# SAS_Connectors.net
KiCad netlist of a schematic drawn in Altium Designer
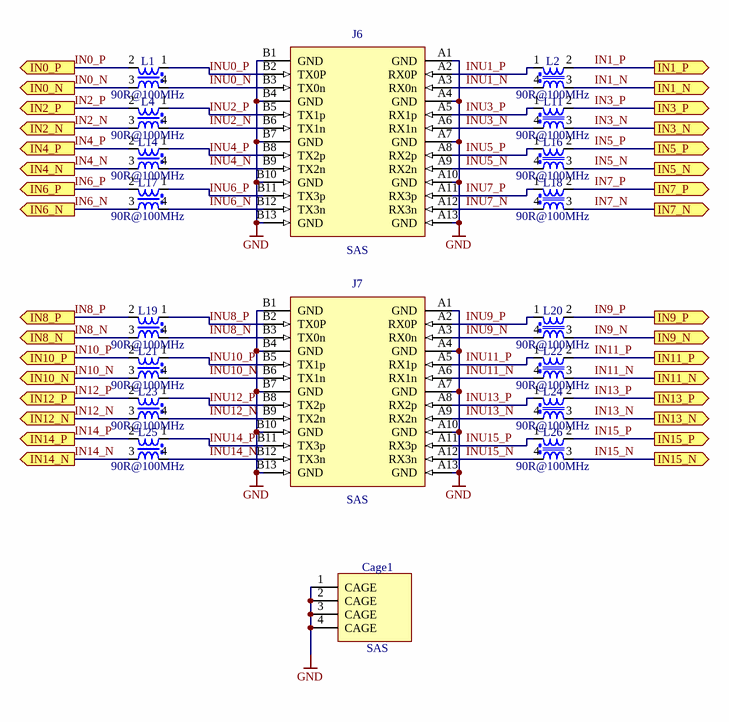
[diagram p0: SAS_Connectors.SchDoc]

(export (version "E")
  (design (tool "Eeschema 10.0.6"))
  (components
    (comp (ref "Cage1")
      (value "SAS")
      (footprint "TYCO_1888321-2")
      (description "SAS 2x1 Cage")
      (fields
        (field (name "PART NUMBER") "TYCO_1888321-2")
        (field (name "MANUFACTURER") "TYCO ELECTRONICS")
        (field (name "AUTHOR") "GK")
      )
      (libsource (lib "LIBRARY_SCH") (part "CON_SAS_Cage"))
    )
    (comp (ref "J6")
      (value "SAS")
      (footprint "TYCO_1761987-7")
      (description "26Position mini SAS Connector")
      (fields
        (field (name "PART NUMBER") "TYCO_1761987-7")
        (field (name "MANUFACTURER") "TYCO ELECTRONICS")
        (field (name "AUTHOR") "GK")
      )
      (libsource (lib "LIBRARY_SCH") (part "CON_SAS_1761987-7"))
    )
    (comp (ref "J7")
      (value "SAS")
      (footprint "TYCO_1761987-7")
      (description "26Position mini SAS Connector")
      (fields
        (field (name "PART NUMBER") "TYCO_1761987-7")
        (field (name "MANUFACTURER") "TYCO ELECTRONICS")
        (field (name "AUTHOR") "GK")
      )
      (libsource (lib "LIBRARY_SCH") (part "CON_SAS_1761987-7"))
    )
    (comp (ref "L1")
      (value "90R@100MHz")
      (footprint "IND_MURATA_DLW21S")
      (description "Inductor Common Mode")
      (fields
        (field (name "PART NUMBER") "IND_MURATA_DLW21SN900SQ2L")
        (field (name "POWER") "330mA")
        (field (name "AUTHOR") "CERN DEM JLC")
      )
      (libsource (lib "") (part "Inductor Common Mode 1Dot-2 4Dot-3_1"))
    )
    (comp (ref "L2")
      (value "90R@100MHz")
      (footprint "IND_MURATA_DLW21S")
      (description "Inductor Common Mode")
      (fields
        (field (name "PART NUMBER") "IND_MURATA_DLW21SN900SQ2L")
        (field (name "POWER") "330mA")
        (field (name "AUTHOR") "CERN DEM JLC")
      )
      (libsource (lib "Inductors & Transformers") (part "Inductor Common Mode 1Dot-2 4Dot-3"))
    )
    (comp (ref "L4")
      (value "90R@100MHz")
      (footprint "IND_MURATA_DLW21S")
      (description "Inductor Common Mode")
      (fields
        (field (name "PART NUMBER") "IND_MURATA_DLW21SN900SQ2L")
        (field (name "POWER") "330mA")
        (field (name "AUTHOR") "CERN DEM JLC")
      )
      (libsource (lib "") (part "Inductor Common Mode 1Dot-2 4Dot-3_1"))
    )
    (comp (ref "L11")
      (value "90R@100MHz")
      (footprint "IND_MURATA_DLW21S")
      (description "Inductor Common Mode")
      (fields
        (field (name "PART NUMBER") "IND_MURATA_DLW21SN900SQ2L")
        (field (name "POWER") "330mA")
        (field (name "AUTHOR") "CERN DEM JLC")
      )
      (libsource (lib "Inductors & Transformers") (part "Inductor Common Mode 1Dot-2 4Dot-3"))
    )
    (comp (ref "L14")
      (value "90R@100MHz")
      (footprint "IND_MURATA_DLW21S")
      (description "Inductor Common Mode")
      (fields
        (field (name "PART NUMBER") "IND_MURATA_DLW21SN900SQ2L")
        (field (name "POWER") "330mA")
        (field (name "AUTHOR") "CERN DEM JLC")
      )
      (libsource (lib "") (part "Inductor Common Mode 1Dot-2 4Dot-3_1"))
    )
    (comp (ref "L16")
      (value "90R@100MHz")
      (footprint "IND_MURATA_DLW21S")
      (description "Inductor Common Mode")
      (fields
        (field (name "PART NUMBER") "IND_MURATA_DLW21SN900SQ2L")
        (field (name "POWER") "330mA")
        (field (name "AUTHOR") "CERN DEM JLC")
      )
      (libsource (lib "Inductors & Transformers") (part "Inductor Common Mode 1Dot-2 4Dot-3"))
    )
    (comp (ref "L17")
      (value "90R@100MHz")
      (footprint "IND_MURATA_DLW21S")
      (description "Inductor Common Mode")
      (fields
        (field (name "PART NUMBER") "IND_MURATA_DLW21SN900SQ2L")
        (field (name "POWER") "330mA")
        (field (name "AUTHOR") "CERN DEM JLC")
      )
      (libsource (lib "") (part "Inductor Common Mode 1Dot-2 4Dot-3_1"))
    )
    (comp (ref "L18")
      (value "90R@100MHz")
      (footprint "IND_MURATA_DLW21S")
      (description "Inductor Common Mode")
      (fields
        (field (name "PART NUMBER") "IND_MURATA_DLW21SN900SQ2L")
        (field (name "POWER") "330mA")
        (field (name "AUTHOR") "CERN DEM JLC")
      )
      (libsource (lib "Inductors & Transformers") (part "Inductor Common Mode 1Dot-2 4Dot-3"))
    )
    (comp (ref "L19")
      (value "90R@100MHz")
      (footprint "IND_MURATA_DLW21S")
      (description "Inductor Common Mode")
      (fields
        (field (name "PART NUMBER") "IND_MURATA_DLW21SN900SQ2L")
        (field (name "POWER") "330mA")
        (field (name "AUTHOR") "CERN DEM JLC")
      )
      (libsource (lib "") (part "Inductor Common Mode 1Dot-2 4Dot-3_1"))
    )
    (comp (ref "L20")
      (value "90R@100MHz")
      (footprint "IND_MURATA_DLW21S")
      (description "Inductor Common Mode")
      (fields
        (field (name "PART NUMBER") "IND_MURATA_DLW21SN900SQ2L")
        (field (name "POWER") "330mA")
        (field (name "AUTHOR") "CERN DEM JLC")
      )
      (libsource (lib "Inductors & Transformers") (part "Inductor Common Mode 1Dot-2 4Dot-3"))
    )
    (comp (ref "L21")
      (value "90R@100MHz")
      (footprint "IND_MURATA_DLW21S")
      (description "Inductor Common Mode")
      (fields
        (field (name "PART NUMBER") "IND_MURATA_DLW21SN900SQ2L")
        (field (name "POWER") "330mA")
        (field (name "AUTHOR") "CERN DEM JLC")
      )
      (libsource (lib "") (part "Inductor Common Mode 1Dot-2 4Dot-3_1"))
    )
    (comp (ref "L22")
      (value "90R@100MHz")
      (footprint "IND_MURATA_DLW21S")
      (description "Inductor Common Mode")
      (fields
        (field (name "PART NUMBER") "IND_MURATA_DLW21SN900SQ2L")
        (field (name "POWER") "330mA")
        (field (name "AUTHOR") "CERN DEM JLC")
      )
      (libsource (lib "Inductors & Transformers") (part "Inductor Common Mode 1Dot-2 4Dot-3"))
    )
    (comp (ref "L23")
      (value "90R@100MHz")
      (footprint "IND_MURATA_DLW21S")
      (description "Inductor Common Mode")
      (fields
        (field (name "PART NUMBER") "IND_MURATA_DLW21SN900SQ2L")
        (field (name "POWER") "330mA")
        (field (name "AUTHOR") "CERN DEM JLC")
      )
      (libsource (lib "") (part "Inductor Common Mode 1Dot-2 4Dot-3_1"))
    )
    (comp (ref "L24")
      (value "90R@100MHz")
      (footprint "IND_MURATA_DLW21S")
      (description "Inductor Common Mode")
      (fields
        (field (name "PART NUMBER") "IND_MURATA_DLW21SN900SQ2L")
        (field (name "POWER") "330mA")
        (field (name "AUTHOR") "CERN DEM JLC")
      )
      (libsource (lib "Inductors & Transformers") (part "Inductor Common Mode 1Dot-2 4Dot-3"))
    )
    (comp (ref "L25")
      (value "90R@100MHz")
      (footprint "IND_MURATA_DLW21S")
      (description "Inductor Common Mode")
      (fields
        (field (name "PART NUMBER") "IND_MURATA_DLW21SN900SQ2L")
        (field (name "POWER") "330mA")
        (field (name "AUTHOR") "CERN DEM JLC")
      )
      (libsource (lib "") (part "Inductor Common Mode 1Dot-2 4Dot-3_1"))
    )
    (comp (ref "L26")
      (value "90R@100MHz")
      (footprint "IND_MURATA_DLW21S")
      (description "Inductor Common Mode")
      (fields
        (field (name "PART NUMBER") "IND_MURATA_DLW21SN900SQ2L")
        (field (name "POWER") "330mA")
        (field (name "AUTHOR") "CERN DEM JLC")
      )
      (libsource (lib "Inductors & Transformers") (part "Inductor Common Mode 1Dot-2 4Dot-3"))
    )
  )
  (nets
    (net (code "1") (name "/IN0_N") (class "Default")
      (node (ref "L1") (pin "3") (pinfunction "3_3") (pintype "passive"))
    )
    (net (code "2") (name "/IN0_P") (class "Default")
      (node (ref "L1") (pin "2") (pinfunction "2_2") (pintype "passive"))
    )
    (net (code "3") (name "/IN1_N") (class "Default")
      (node (ref "L2") (pin "3") (pinfunction "3_3") (pintype "passive"))
    )
    (net (code "4") (name "/IN1_P") (class "Default")
      (node (ref "L2") (pin "2") (pinfunction "2_2") (pintype "passive"))
    )
    (net (code "5") (name "/IN2_N") (class "Default")
      (node (ref "L4") (pin "3") (pinfunction "3_3") (pintype "passive"))
    )
    (net (code "6") (name "/IN2_P") (class "Default")
      (node (ref "L4") (pin "2") (pinfunction "2_2") (pintype "passive"))
    )
    (net (code "7") (name "/IN3_N") (class "Default")
      (node (ref "L11") (pin "3") (pinfunction "3_3") (pintype "passive"))
    )
    (net (code "8") (name "/IN3_P") (class "Default")
      (node (ref "L11") (pin "2") (pinfunction "2_2") (pintype "passive"))
    )
    (net (code "9") (name "/IN4_N") (class "Default")
      (node (ref "L14") (pin "3") (pinfunction "3_3") (pintype "passive"))
    )
    (net (code "10") (name "/IN4_P") (class "Default")
      (node (ref "L14") (pin "2") (pinfunction "2_2") (pintype "passive"))
    )
    (net (code "11") (name "/IN5_N") (class "Default")
      (node (ref "L16") (pin "3") (pinfunction "3_3") (pintype "passive"))
    )
    (net (code "12") (name "/IN5_P") (class "Default")
      (node (ref "L16") (pin "2") (pinfunction "2_2") (pintype "passive"))
    )
    (net (code "13") (name "/IN6_N") (class "Default")
      (node (ref "L17") (pin "3") (pinfunction "3_3") (pintype "passive"))
    )
    (net (code "14") (name "/IN6_P") (class "Default")
      (node (ref "L17") (pin "2") (pinfunction "2_2") (pintype "passive"))
    )
    (net (code "15") (name "/IN7_N") (class "Default")
      (node (ref "L18") (pin "3") (pinfunction "3_3") (pintype "passive"))
    )
    (net (code "16") (name "/IN7_P") (class "Default")
      (node (ref "L18") (pin "2") (pinfunction "2_2") (pintype "passive"))
    )
    (net (code "17") (name "/IN8_N") (class "Default")
      (node (ref "L19") (pin "3") (pinfunction "3_3") (pintype "passive"))
    )
    (net (code "18") (name "/IN8_P") (class "Default")
      (node (ref "L19") (pin "2") (pinfunction "2_2") (pintype "passive"))
    )
    (net (code "19") (name "/IN9_N") (class "Default")
      (node (ref "L20") (pin "3") (pinfunction "3_3") (pintype "passive"))
    )
    (net (code "20") (name "/IN9_P") (class "Default")
      (node (ref "L20") (pin "2") (pinfunction "2_2") (pintype "passive"))
    )
    (net (code "21") (name "/IN10_N") (class "Default")
      (node (ref "L21") (pin "3") (pinfunction "3_3") (pintype "passive"))
    )
    (net (code "22") (name "/IN10_P") (class "Default")
      (node (ref "L21") (pin "2") (pinfunction "2_2") (pintype "passive"))
    )
    (net (code "23") (name "/IN11_N") (class "Default")
      (node (ref "L22") (pin "3") (pinfunction "3_3") (pintype "passive"))
    )
    (net (code "24") (name "/IN11_P") (class "Default")
      (node (ref "L22") (pin "2") (pinfunction "2_2") (pintype "passive"))
    )
    (net (code "25") (name "/IN12_N") (class "Default")
      (node (ref "L23") (pin "3") (pinfunction "3_3") (pintype "passive"))
    )
    (net (code "26") (name "/IN12_P") (class "Default")
      (node (ref "L23") (pin "2") (pinfunction "2_2") (pintype "passive"))
    )
    (net (code "27") (name "/IN13_N") (class "Default")
      (node (ref "L24") (pin "3") (pinfunction "3_3") (pintype "passive"))
    )
    (net (code "28") (name "/IN13_P") (class "Default")
      (node (ref "L24") (pin "2") (pinfunction "2_2") (pintype "passive"))
    )
    (net (code "29") (name "/IN14_N") (class "Default")
      (node (ref "L25") (pin "3") (pinfunction "3_3") (pintype "passive"))
    )
    (net (code "30") (name "/IN14_P") (class "Default")
      (node (ref "L25") (pin "2") (pinfunction "2_2") (pintype "passive"))
    )
    (net (code "31") (name "/IN15_N") (class "Default")
      (node (ref "L26") (pin "3") (pinfunction "3_3") (pintype "passive"))
    )
    (net (code "32") (name "/IN15_P") (class "Default")
      (node (ref "L26") (pin "2") (pinfunction "2_2") (pintype "passive"))
    )
    (net (code "33") (name "/INU0_N") (class "Default")
      (node (ref "J6") (pin "B3") (pinfunction "TX0n_B3") (pintype "input"))
      (node (ref "L1") (pin "4") (pinfunction "4_4") (pintype "passive"))
    )
    (net (code "34") (name "/INU0_P") (class "Default")
      (node (ref "J6") (pin "B2") (pinfunction "TX0P_B2") (pintype "input"))
      (node (ref "L1") (pin "1") (pinfunction "1_1") (pintype "passive"))
    )
    (net (code "35") (name "/INU1_N") (class "Default")
      (node (ref "J6") (pin "A3") (pinfunction "RX0n_A3") (pintype "input"))
      (node (ref "L2") (pin "4") (pinfunction "4_4") (pintype "passive"))
    )
    (net (code "36") (name "/INU1_P") (class "Default")
      (node (ref "J6") (pin "A2") (pinfunction "RX0P_A2") (pintype "input"))
      (node (ref "L2") (pin "1") (pinfunction "1_1") (pintype "passive"))
    )
    (net (code "37") (name "/INU2_N") (class "Default")
      (node (ref "J6") (pin "B6") (pinfunction "TX1n_B6") (pintype "input"))
      (node (ref "L4") (pin "4") (pinfunction "4_4") (pintype "passive"))
    )
    (net (code "38") (name "/INU2_P") (class "Default")
      (node (ref "J6") (pin "B5") (pinfunction "TX1p_B5") (pintype "input"))
      (node (ref "L4") (pin "1") (pinfunction "1_1") (pintype "passive"))
    )
    (net (code "39") (name "/INU3_N") (class "Default")
      (node (ref "J6") (pin "A6") (pinfunction "RX1n_A6") (pintype "input"))
      (node (ref "L11") (pin "4") (pinfunction "4_4") (pintype "passive"))
    )
    (net (code "40") (name "/INU3_P") (class "Default")
      (node (ref "J6") (pin "A5") (pinfunction "RX1p_A5") (pintype "input"))
      (node (ref "L11") (pin "1") (pinfunction "1_1") (pintype "passive"))
    )
    (net (code "41") (name "/INU4_N") (class "Default")
      (node (ref "J6") (pin "B9") (pinfunction "TX2n_B9") (pintype "input"))
      (node (ref "L14") (pin "4") (pinfunction "4_4") (pintype "passive"))
    )
    (net (code "42") (name "/INU4_P") (class "Default")
      (node (ref "J6") (pin "B8") (pinfunction "TX2p_B8") (pintype "input"))
      (node (ref "L14") (pin "1") (pinfunction "1_1") (pintype "passive"))
    )
    (net (code "43") (name "/INU5_N") (class "Default")
      (node (ref "J6") (pin "A9") (pinfunction "RX2n_A9") (pintype "input"))
      (node (ref "L16") (pin "4") (pinfunction "4_4") (pintype "passive"))
    )
    (net (code "44") (name "/INU5_P") (class "Default")
      (node (ref "J6") (pin "A8") (pinfunction "RX2p_A8") (pintype "input"))
      (node (ref "L16") (pin "1") (pinfunction "1_1") (pintype "passive"))
    )
    (net (code "45") (name "/INU6_N") (class "Default")
      (node (ref "J6") (pin "B12") (pinfunction "TX3n_B12") (pintype "input"))
      (node (ref "L17") (pin "4") (pinfunction "4_4") (pintype "passive"))
    )
    (net (code "46") (name "/INU6_P") (class "Default")
      (node (ref "J6") (pin "B11") (pinfunction "TX3p_B11") (pintype "input"))
      (node (ref "L17") (pin "1") (pinfunction "1_1") (pintype "passive"))
    )
    (net (code "47") (name "/INU7_N") (class "Default")
      (node (ref "J6") (pin "A12") (pinfunction "RX3n_A12") (pintype "input"))
      (node (ref "L18") (pin "4") (pinfunction "4_4") (pintype "passive"))
    )
    (net (code "48") (name "/INU7_P") (class "Default")
      (node (ref "J6") (pin "A11") (pinfunction "RX3p_A11") (pintype "input"))
      (node (ref "L18") (pin "1") (pinfunction "1_1") (pintype "passive"))
    )
    (net (code "49") (name "/INU8_N") (class "Default")
      (node (ref "J7") (pin "B3") (pinfunction "TX0n_B3") (pintype "input"))
      (node (ref "L19") (pin "4") (pinfunction "4_4") (pintype "passive"))
    )
    (net (code "50") (name "/INU8_P") (class "Default")
      (node (ref "J7") (pin "B2") (pinfunction "TX0P_B2") (pintype "input"))
      (node (ref "L19") (pin "1") (pinfunction "1_1") (pintype "passive"))
    )
    (net (code "51") (name "/INU9_N") (class "Default")
      (node (ref "J7") (pin "A3") (pinfunction "RX0n_A3") (pintype "input"))
      (node (ref "L20") (pin "4") (pinfunction "4_4") (pintype "passive"))
    )
    (net (code "52") (name "/INU9_P") (class "Default")
      (node (ref "J7") (pin "A2") (pinfunction "RX0P_A2") (pintype "input"))
      (node (ref "L20") (pin "1") (pinfunction "1_1") (pintype "passive"))
    )
    (net (code "53") (name "/INU10_N") (class "Default")
      (node (ref "J7") (pin "B6") (pinfunction "TX1n_B6") (pintype "input"))
      (node (ref "L21") (pin "4") (pinfunction "4_4") (pintype "passive"))
    )
    (net (code "54") (name "/INU10_P") (class "Default")
      (node (ref "J7") (pin "B5") (pinfunction "TX1p_B5") (pintype "input"))
      (node (ref "L21") (pin "1") (pinfunction "1_1") (pintype "passive"))
    )
    (net (code "55") (name "/INU11_N") (class "Default")
      (node (ref "J7") (pin "A6") (pinfunction "RX1n_A6") (pintype "input"))
      (node (ref "L22") (pin "4") (pinfunction "4_4") (pintype "passive"))
    )
    (net (code "56") (name "/INU11_P") (class "Default")
      (node (ref "J7") (pin "A5") (pinfunction "RX1p_A5") (pintype "input"))
      (node (ref "L22") (pin "1") (pinfunction "1_1") (pintype "passive"))
    )
    (net (code "57") (name "/INU12_N") (class "Default")
      (node (ref "J7") (pin "B9") (pinfunction "TX2n_B9") (pintype "input"))
      (node (ref "L23") (pin "4") (pinfunction "4_4") (pintype "passive"))
    )
    (net (code "58") (name "/INU12_P") (class "Default")
      (node (ref "J7") (pin "B8") (pinfunction "TX2p_B8") (pintype "input"))
      (node (ref "L23") (pin "1") (pinfunction "1_1") (pintype "passive"))
    )
    (net (code "59") (name "/INU13_N") (class "Default")
      (node (ref "J7") (pin "A9") (pinfunction "RX2n_A9") (pintype "input"))
      (node (ref "L24") (pin "4") (pinfunction "4_4") (pintype "passive"))
    )
    (net (code "60") (name "/INU13_P") (class "Default")
      (node (ref "J7") (pin "A8") (pinfunction "RX2p_A8") (pintype "input"))
      (node (ref "L24") (pin "1") (pinfunction "1_1") (pintype "passive"))
    )
    (net (code "61") (name "/INU14_N") (class "Default")
      (node (ref "J7") (pin "B12") (pinfunction "TX3n_B12") (pintype "input"))
      (node (ref "L25") (pin "4") (pinfunction "4_4") (pintype "passive"))
    )
    (net (code "62") (name "/INU14_P") (class "Default")
      (node (ref "J7") (pin "B11") (pinfunction "TX3p_B11") (pintype "input"))
      (node (ref "L25") (pin "1") (pinfunction "1_1") (pintype "passive"))
    )
    (net (code "63") (name "/INU15_N") (class "Default")
      (node (ref "J7") (pin "A12") (pinfunction "RX3n_A12") (pintype "input"))
      (node (ref "L26") (pin "4") (pinfunction "4_4") (pintype "passive"))
    )
    (net (code "64") (name "/INU15_P") (class "Default")
      (node (ref "J7") (pin "A11") (pinfunction "RX3p_A11") (pintype "input"))
      (node (ref "L26") (pin "1") (pinfunction "1_1") (pintype "passive"))
    )
    (net (code "65") (name "GND") (class "Default")
      (node (ref "Cage1") (pin "1") (pinfunction "CAGE_1") (pintype "power_in"))
      (node (ref "Cage1") (pin "2") (pinfunction "CAGE_2") (pintype "power_in"))
      (node (ref "Cage1") (pin "3") (pinfunction "CAGE_3") (pintype "power_in"))
      (node (ref "Cage1") (pin "4") (pinfunction "CAGE_4") (pintype "power_in"))
      (node (ref "J6") (pin "A1") (pinfunction "GND_A1") (pintype "power_in"))
      (node (ref "J6") (pin "A10") (pinfunction "GND_A10") (pintype "input"))
      (node (ref "J6") (pin "A13") (pinfunction "GND_A13") (pintype "input"))
      (node (ref "J6") (pin "A4") (pinfunction "GND_A4") (pintype "power_in"))
      (node (ref "J6") (pin "A7") (pinfunction "GND_A7") (pintype "power_in"))
      (node (ref "J6") (pin "B1") (pinfunction "GND_B1") (pintype "power_in"))
      (node (ref "J6") (pin "B10") (pinfunction "GND_B10") (pintype "input"))
      (node (ref "J6") (pin "B13") (pinfunction "GND_B13") (pintype "input"))
      (node (ref "J6") (pin "B4") (pinfunction "GND_B4") (pintype "power_in"))
      (node (ref "J6") (pin "B7") (pinfunction "GND_B7") (pintype "power_in"))
      (node (ref "J7") (pin "A1") (pinfunction "GND_A1") (pintype "power_in"))
      (node (ref "J7") (pin "A10") (pinfunction "GND_A10") (pintype "input"))
      (node (ref "J7") (pin "A13") (pinfunction "GND_A13") (pintype "input"))
      (node (ref "J7") (pin "A4") (pinfunction "GND_A4") (pintype "power_in"))
      (node (ref "J7") (pin "A7") (pinfunction "GND_A7") (pintype "power_in"))
      (node (ref "J7") (pin "B1") (pinfunction "GND_B1") (pintype "power_in"))
      (node (ref "J7") (pin "B10") (pinfunction "GND_B10") (pintype "input"))
      (node (ref "J7") (pin "B13") (pinfunction "GND_B13") (pintype "input"))
      (node (ref "J7") (pin "B4") (pinfunction "GND_B4") (pintype "power_in"))
      (node (ref "J7") (pin "B7") (pinfunction "GND_B7") (pintype "power_in"))
    )
  )
)
